# Distortion_Effect_Circuit.net
KiCad netlist of a schematic drawn in Altium Designer
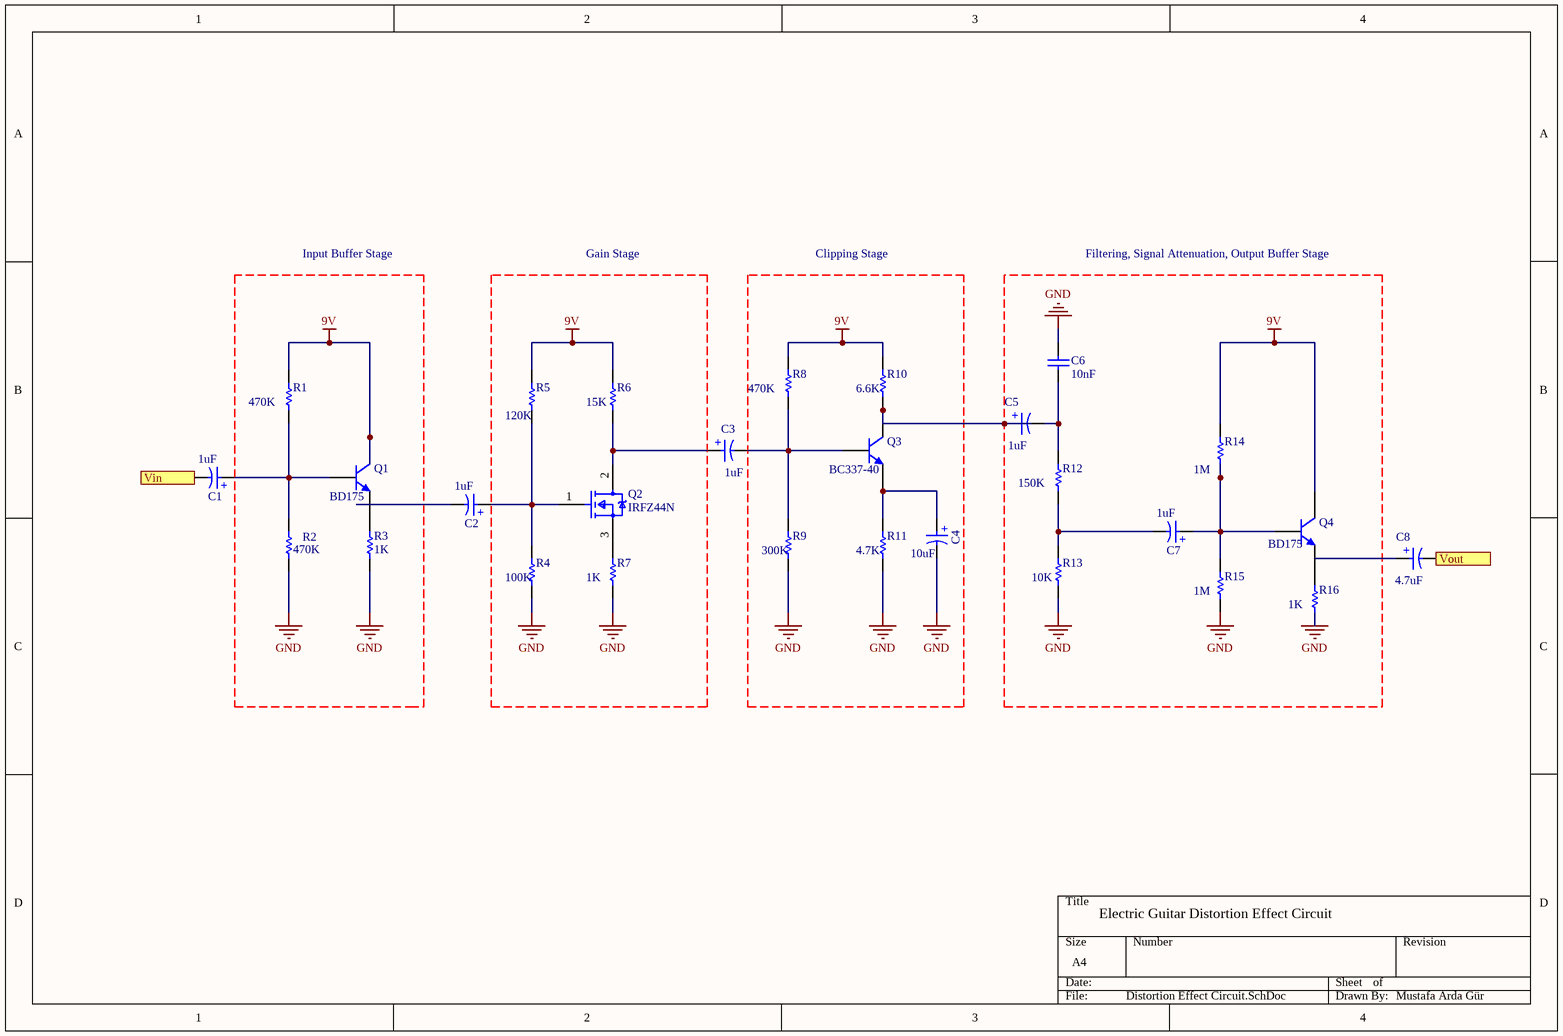
[diagram p0: Distortion Effect Circuit.SchDoc]

(export (version "E")
  (design (tool "Eeschema 10.0.6"))
  (components
    (comp (ref "C1")
      (value "1uF")
      (footprint "WCAP-ATG5_D5H11")
      (description "WCAP-ATG5 Aluminum Electrolytic Capacitors")
      (fields (field (name "TOLERANCE") "20%"))
      (libsource (lib "Altium Content Vault") (part "Capacitor_Polarized"))
    )
    (comp (ref "C2")
      (value "1uF")
      (footprint "WCAP-ATG5_D5H11")
      (description "WCAP-ATG5 Aluminum Electrolytic Capacitors")
      (fields (field (name "TOLERANCE") "20%"))
      (libsource (lib "Altium Content Vault") (part "Capacitor_Polarized"))
    )
    (comp (ref "C3")
      (value "1uF")
      (footprint "WCAP-ATG5_D5H11")
      (description "WCAP-ATG5 Aluminum Electrolytic Capacitors")
      (fields (field (name "TOLERANCE") "20%"))
      (libsource (lib "Altium Content Vault") (part "Capacitor_Polarized"))
    )
    (comp (ref "C4")
      (value "10uF")
      (footprint "WCAP-ATG5_D5H11")
      (description "WCAP-ATG5 Aluminum Electrolytic Capacitors")
      (fields (field (name "TOLERANCE") "20%"))
      (libsource (lib "Altium Content Vault") (part "Capacitor_Polarized"))
    )
    (comp (ref "C5")
      (value "1uF")
      (footprint "WCAP-ATG5_D5H11")
      (description "WCAP-ATG5 Aluminum Electrolytic Capacitors")
      (fields (field (name "TOLERANCE") "20%"))
      (libsource (lib "Altium Content Vault") (part "Capacitor_Polarized"))
    )
    (comp (ref "C6")
      (value "10nF")
      (description "Capacitor")
      (libsource (lib "Simulation Generic Components") (part "Capacitor"))
    )
    (comp (ref "C7")
      (value "1uF")
      (footprint "WCAP-ATG5_D5H11")
      (description "WCAP-ATG5 Aluminum Electrolytic Capacitors")
      (fields (field (name "TOLERANCE") "20%"))
      (libsource (lib "Altium Content Vault") (part "Capacitor_Polarized"))
    )
    (comp (ref "C8")
      (value "4.7uF")
      (footprint "WCAP-ATG5_D5H11")
      (description "WCAP-ATG5 Aluminum Electrolytic Capacitors")
      (fields (field (name "TOLERANCE") "20%"))
      (libsource (lib "Altium Content Vault") (part "Capacitor_Polarized"))
    )
    (comp (ref "Q1")
      (value "BD175")
      (description "Bipolar NPN 3 Pins Transistor VBIC Model")
      (libsource (lib "Simulation Generic Components") (part "BJT NPN VBIC"))
    )
    (comp (ref "Q2")
      (value "IRFZ44N")
      (footprint "FP-PG-TO262-3-MFG")
      (description "IRFZ44NLPBF Single N-Channel 55 V 17.5 mOhm 63 nC HEXFET® Power Mosfet - TO-262")
      (libsource (lib "Altium Content Vault") (part "b09f7f152735e370c1ea22a33fa83d6"))
    )
    (comp (ref "Q3")
      (value "BC337-40")
      (description "Bipolar NPN 3 Pins Transistor VBIC Model")
      (libsource (lib "Simulation Generic Components") (part "BJT NPN VBIC"))
    )
    (comp (ref "Q4")
      (value "BD175")
      (description "Bipolar NPN 3 Pins Transistor VBIC Model")
      (libsource (lib "Simulation Generic Components") (part "BJT NPN VBIC"))
    )
    (comp (ref "R1")
      (value "470K")
      (description "Resistor")
      (libsource (lib "Simulation Generic Components") (part "Resistor"))
    )
    (comp (ref "R2")
      (value "470K")
      (description "Resistor")
      (libsource (lib "Simulation Generic Components") (part "Resistor"))
    )
    (comp (ref "R3")
      (value "1K")
      (description "Resistor")
      (libsource (lib "Simulation Generic Components") (part "Resistor"))
    )
    (comp (ref "R4")
      (value "100K")
      (description "Resistor")
      (libsource (lib "Simulation Generic Components") (part "Resistor"))
    )
    (comp (ref "R5")
      (value "120K")
      (description "Resistor")
      (libsource (lib "Simulation Generic Components") (part "Resistor"))
    )
    (comp (ref "R6")
      (value "15K")
      (description "Resistor")
      (libsource (lib "Simulation Generic Components") (part "Resistor"))
    )
    (comp (ref "R7")
      (value "1K")
      (description "Resistor")
      (libsource (lib "Simulation Generic Components") (part "Resistor"))
    )
    (comp (ref "R8")
      (value "470K")
      (description "Resistor")
      (libsource (lib "Simulation Generic Components") (part "Resistor"))
    )
    (comp (ref "R9")
      (value "300K")
      (description "Resistor")
      (libsource (lib "Simulation Generic Components") (part "Resistor"))
    )
    (comp (ref "R10")
      (value "6.6K")
      (description "Resistor")
      (libsource (lib "Simulation Generic Components") (part "Resistor"))
    )
    (comp (ref "R11")
      (value "4.7K")
      (description "Resistor")
      (libsource (lib "Simulation Generic Components") (part "Resistor"))
    )
    (comp (ref "R12")
      (value "150K")
      (description "Resistor")
      (libsource (lib "Simulation Generic Components") (part "Resistor"))
    )
    (comp (ref "R13")
      (value "10K")
      (description "Resistor")
      (libsource (lib "Simulation Generic Components") (part "Resistor"))
    )
    (comp (ref "R14")
      (value "1M")
      (description "Resistor")
      (libsource (lib "Simulation Generic Components") (part "Resistor"))
    )
    (comp (ref "R15")
      (value "1M")
      (description "Resistor")
      (libsource (lib "Simulation Generic Components") (part "Resistor"))
    )
    (comp (ref "R16")
      (value "1K")
      (description "Resistor")
      (libsource (lib "Simulation Generic Components") (part "Resistor"))
    )
  )
  (nets
    (net (code "1") (name "/Vin") (class "Default")
      (node (ref "C1") (pin "2") (pinfunction "N_2") (pintype "passive"))
    )
    (net (code "2") (name "/Vout") (class "Default")
      (node (ref "C8") (pin "2") (pinfunction "N_2") (pintype "passive"))
    )
    (net (code "3") (name "9V") (class "Default")
      (node (ref "Q1") (pin "1") (pinfunction "C_1") (pintype "passive"))
      (node (ref "Q4") (pin "1") (pinfunction "C_1") (pintype "passive"))
      (node (ref "R1") (pin "2") (pinfunction "2_2") (pintype "passive"))
      (node (ref "R10") (pin "2") (pinfunction "2_2") (pintype "passive"))
      (node (ref "R14") (pin "2") (pinfunction "2_2") (pintype "passive"))
      (node (ref "R5") (pin "2") (pinfunction "2_2") (pintype "passive"))
      (node (ref "R6") (pin "2") (pinfunction "2_2") (pintype "passive"))
      (node (ref "R8") (pin "2") (pinfunction "2_2") (pintype "passive"))
    )
    (net (code "4") (name "GND") (class "Default")
      (node (ref "C4") (pin "2") (pinfunction "N_2") (pintype "passive"))
      (node (ref "C6") (pin "2") (pinfunction "2_2") (pintype "passive"))
      (node (ref "R11") (pin "1") (pinfunction "1_1") (pintype "passive"))
      (node (ref "R13") (pin "1") (pinfunction "1_1") (pintype "passive"))
      (node (ref "R15") (pin "1") (pinfunction "1_1") (pintype "passive"))
      (node (ref "R16") (pin "1") (pinfunction "1_1") (pintype "passive"))
      (node (ref "R2") (pin "1") (pinfunction "1_1") (pintype "passive"))
      (node (ref "R3") (pin "1") (pinfunction "1_1") (pintype "passive"))
      (node (ref "R4") (pin "1") (pinfunction "1_1") (pintype "passive"))
      (node (ref "R7") (pin "1") (pinfunction "1_1") (pintype "passive"))
      (node (ref "R9") (pin "1") (pinfunction "1_1") (pintype "passive"))
    )
    (net (code "5") (name "Net-(C1-P)") (class "Default")
      (node (ref "C1") (pin "1") (pinfunction "P_1") (pintype "passive"))
      (node (ref "Q1") (pin "2") (pinfunction "B_2") (pintype "passive"))
      (node (ref "R1") (pin "1") (pinfunction "1_1") (pintype "passive"))
      (node (ref "R2") (pin "2") (pinfunction "2_2") (pintype "passive"))
    )
    (net (code "6") (name "Net-(C2-P)") (class "Default")
      (node (ref "C2") (pin "1") (pinfunction "P_1") (pintype "passive"))
      (node (ref "Q2") (pin "1") (pinfunction "G_1") (pintype "passive"))
      (node (ref "R4") (pin "2") (pinfunction "2_2") (pintype "passive"))
      (node (ref "R5") (pin "1") (pinfunction "1_1") (pintype "passive"))
    )
    (net (code "7") (name "Net-(C3-N)") (class "Default")
      (node (ref "C3") (pin "2") (pinfunction "N_2") (pintype "passive"))
      (node (ref "Q3") (pin "2") (pinfunction "B_2") (pintype "passive"))
      (node (ref "R8") (pin "1") (pinfunction "1_1") (pintype "passive"))
      (node (ref "R9") (pin "2") (pinfunction "2_2") (pintype "passive"))
    )
    (net (code "8") (name "Net-(C3-P)") (class "Default")
      (node (ref "C3") (pin "1") (pinfunction "P_1") (pintype "passive"))
      (node (ref "Q2") (pin "2") (pinfunction "D_2") (pintype "passive"))
      (node (ref "R6") (pin "1") (pinfunction "1_1") (pintype "passive"))
    )
    (net (code "9") (name "Net-(C4-P)") (class "Default")
      (node (ref "C4") (pin "1") (pinfunction "P_1") (pintype "passive"))
      (node (ref "Q3") (pin "3") (pinfunction "E_3") (pintype "passive"))
      (node (ref "R11") (pin "2") (pinfunction "2_2") (pintype "passive"))
    )
    (net (code "10") (name "Net-(C5-N)") (class "Default")
      (node (ref "C5") (pin "2") (pinfunction "N_2") (pintype "passive"))
      (node (ref "C6") (pin "1") (pinfunction "1_1") (pintype "passive"))
      (node (ref "R12") (pin "2") (pinfunction "2_2") (pintype "passive"))
    )
    (net (code "11") (name "Net-(C5-P)") (class "Default")
      (node (ref "C5") (pin "1") (pinfunction "P_1") (pintype "passive"))
      (node (ref "Q3") (pin "1") (pinfunction "C_1") (pintype "passive"))
      (node (ref "R10") (pin "1") (pinfunction "1_1") (pintype "passive"))
    )
    (net (code "12") (name "Net-(C7-N)") (class "Default")
      (node (ref "C7") (pin "2") (pinfunction "N_2") (pintype "passive"))
      (node (ref "R12") (pin "1") (pinfunction "1_1") (pintype "passive"))
      (node (ref "R13") (pin "2") (pinfunction "2_2") (pintype "passive"))
    )
    (net (code "13") (name "Net-(C7-P)") (class "Default")
      (node (ref "C7") (pin "1") (pinfunction "P_1") (pintype "passive"))
      (node (ref "Q4") (pin "2") (pinfunction "B_2") (pintype "passive"))
      (node (ref "R14") (pin "1") (pinfunction "1_1") (pintype "passive"))
      (node (ref "R15") (pin "2") (pinfunction "2_2") (pintype "passive"))
    )
    (net (code "14") (name "Net-(Q1-E)") (class "Default")
      (node (ref "Q1") (pin "3") (pinfunction "E_3") (pintype "passive"))
      (node (ref "R3") (pin "2") (pinfunction "2_2") (pintype "passive"))
    )
    (net (code "15") (name "Net-(Q2-S)") (class "Default")
      (node (ref "Q2") (pin "3") (pinfunction "S_3") (pintype "passive"))
      (node (ref "R7") (pin "2") (pinfunction "2_2") (pintype "passive"))
    )
    (net (code "16") (name "Net-(Q4-E)") (class "Default")
      (node (ref "Q4") (pin "3") (pinfunction "E_3") (pintype "passive"))
      (node (ref "R16") (pin "2") (pinfunction "2_2") (pintype "passive"))
    )
    (net (code "17") (name "unconnected-(C2-N-Pad2)") (class "Default")
      (node (ref "C2") (pin "2") (pinfunction "N_2") (pintype "passive"))
    )
    (net (code "18") (name "unconnected-(C8-P-Pad1)") (class "Default")
      (node (ref "C8") (pin "1") (pinfunction "P_1") (pintype "passive"))
    )
  )
)
